# mySensor.net
KiCad netlist of a schematic drawn in Altium Designer
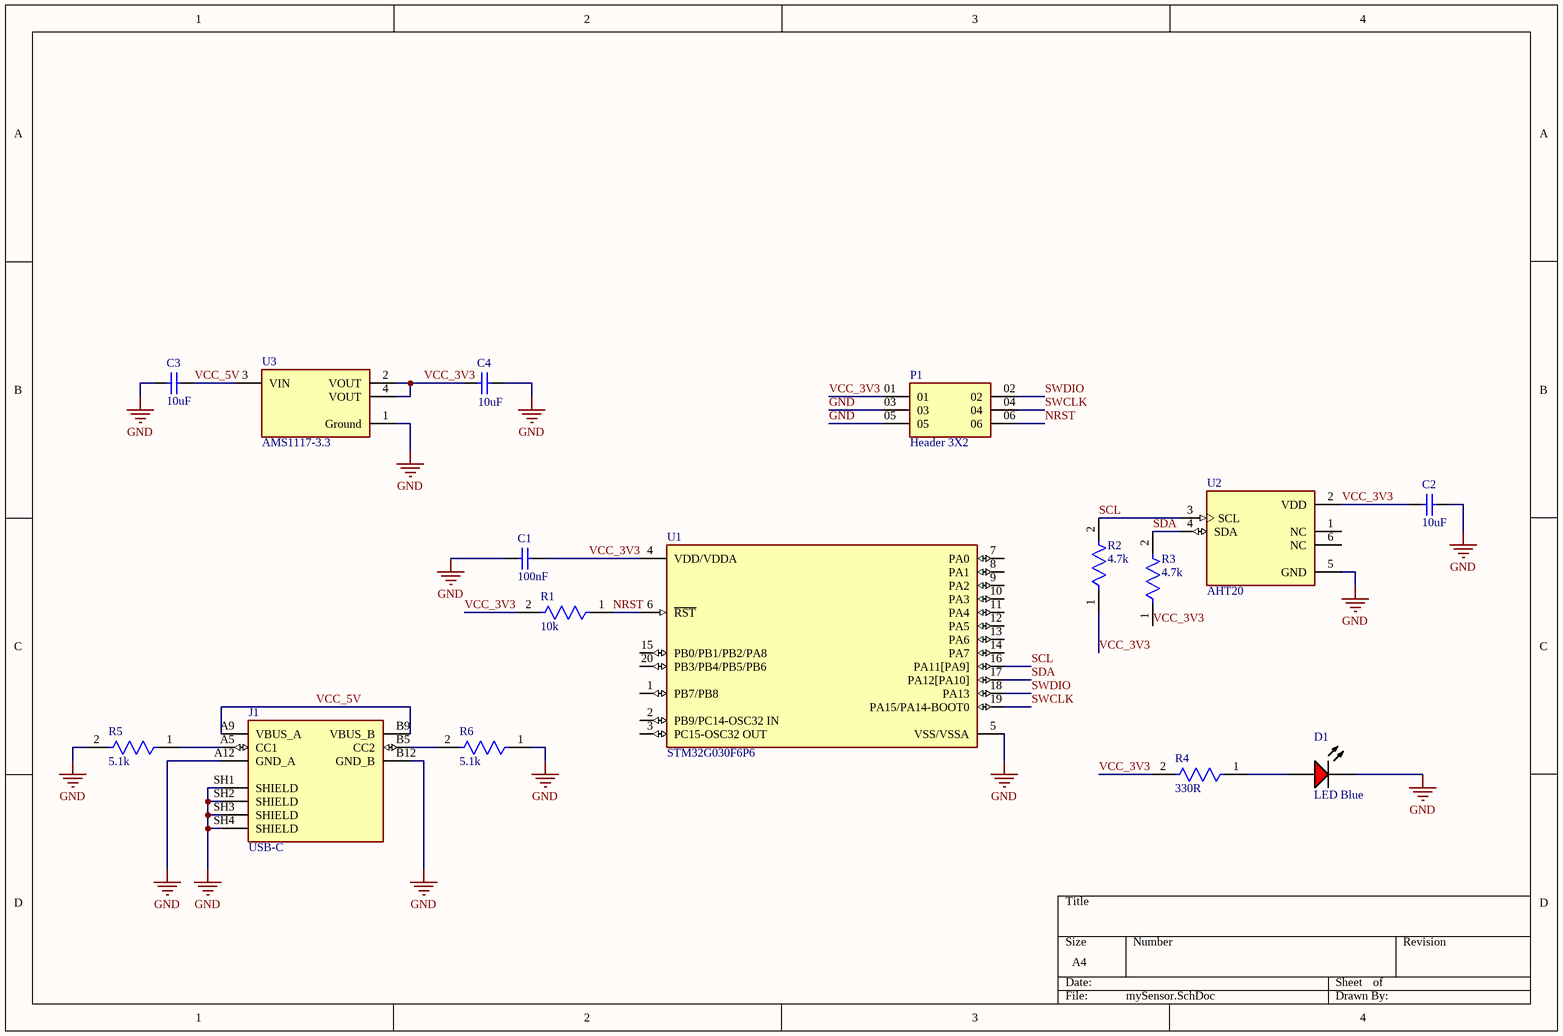
[diagram p0: mySensor.SchDoc]

(export (version "E")
  (design (tool "Eeschema 10.0.6"))
  (components
    (comp (ref "C1")
      (value "100nF")
      (footprint "CAPC1206(3216)190_L")
      (description "CAP 100nF")
      (fields (field (name "TOLERANCE") "Â±20%"))
      (libsource (lib "Altium Content Vault") (part "CAP"))
    )
    (comp (ref "C2")
      (value "10uF")
      (footprint "CAPC1206(3216)190_L")
      (description "CAP 10uF 6.3V ±20% 1206 (3216 Metric) Thickness 1.9mm SMD")
      (fields (field (name "TOLERANCE") "Â±20%"))
      (libsource (lib "Altium Content Vault") (part "CAP"))
    )
    (comp (ref "C3")
      (value "10uF")
      (footprint "CAPC1206(3216)190_L")
      (description "CAP 10uF 6.3V ±20% 1206 (3216 Metric) Thickness 1.9mm SMD")
      (fields (field (name "TOLERANCE") "Â±20%"))
      (libsource (lib "Altium Content Vault") (part "CAP"))
    )
    (comp (ref "C4")
      (value "10uF")
      (footprint "CAPC1206(3216)190_L")
      (description "CAP 10uF 6.3V ±20% 1206 (3216 Metric) Thickness 1.9mm SMD")
      (fields (field (name "TOLERANCE") "Â±20%"))
      (libsource (lib "Altium Content Vault") (part "CAP"))
    )
    (comp (ref "D1")
      (value "LED Blue")
      (footprint "LUMX-SML-LX1206IC_V")
      (description "LED Red, 65 mW, -40 to 85 degC, 2-Pin SMD, RoHS, Tape and Reel")
      (fields (field (name "MANUFACTURER") "Lumex") (field (name "PART NO") "SML-LX1206IC-TR"))
      (libsource (lib "Altium Content Vault") (part "LED-RED-AK-2"))
    )
    (comp (ref "J1")
      (value "USB-C")
      (footprint "AMPHENOL_10164359-00011LF")
      (description "USB Type C Receptacle SMT Single Row 6Pin")
      (fields (field (name "MF") "Amphenol") (field (name "MP") "1016435900011LF"))
      (libsource (lib "10164359-00011LF") (part "10164359-00011LF"))
    )
    (comp (ref "P1")
      (value "Header 3X2")
      (footprint "SAMTEC_TSM-103-02-T-DV-LC")
      (description "Conn Unshrouded Header HDR 6 POS 2.54mm Solder ST SMD Tube")
      (fields (field (name "MF") "Samtec") (field (name "MP") "TSM-103-02-T-DV-LC"))
      (libsource (lib "TSM-103-02-T-DV-LC") (part "TSM-103-02-T-DV-LC"))
    )
    (comp (ref "R1")
      (value "10k")
      (footprint "FP-CRGCQ1206-IPC_A")
      (description "CRGCQ 1206 10k 5%")
      (fields
        (field (name "MANUFACTURER") "TE Connectivity")
        (field (name "OCTOPART") "https://octopart.com/crgcq1206j4k7-te+connectivity-91018336")
      )
      (libsource (lib "Altium Content Vault") (part "1029c3af85768c4190bb7ad29bc67b5"))
    )
    (comp (ref "R2")
      (value "4.7k")
      (footprint "FP-CRGCQ1206-IPC_A")
      (description "CRGCQ 1206 4K7 5%")
      (fields
        (field (name "MANUFACTURER") "TE Connectivity")
        (field (name "OCTOPART") "https://octopart.com/crgcq1206j4k7-te+connectivity-91018336")
      )
      (libsource (lib "Altium Content Vault") (part "1029c3af85768c4190bb7ad29bc67b5"))
    )
    (comp (ref "R3")
      (value "4.7k")
      (footprint "FP-CRGCQ1206-IPC_A")
      (description "CRGCQ 1206 4K7 5%")
      (fields
        (field (name "MANUFACTURER") "TE Connectivity")
        (field (name "OCTOPART") "https://octopart.com/crgcq1206j4k7-te+connectivity-91018336")
      )
      (libsource (lib "Altium Content Vault") (part "1029c3af85768c4190bb7ad29bc67b5"))
    )
    (comp (ref "R4")
      (value "330R")
      (footprint "FP-CRGCQ1206-IPC_A")
      (description "CRGCQ 1206 330R 5%")
      (fields
        (field (name "MANUFACTURER") "TE Connectivity")
        (field (name "OCTOPART") "https://octopart.com/crgcq1206j4k7-te+connectivity-91018336")
      )
      (libsource (lib "Altium Content Vault") (part "1029c3af85768c4190bb7ad29bc67b5"))
    )
    (comp (ref "R5")
      (value "5.1k")
      (footprint "FP-CRGCQ1206-IPC_A")
      (description "CRGCQ 1206 5K1 5%")
      (fields
        (field (name "MANUFACTURER") "TE Connectivity")
        (field (name "OCTOPART") "https://octopart.com/crgcq1206j4k7-te+connectivity-91018336")
      )
      (libsource (lib "Altium Content Vault") (part "1029c3af85768c4190bb7ad29bc67b5"))
    )
    (comp (ref "R6")
      (value "5.1k")
      (footprint "FP-CRGCQ1206-IPC_A")
      (description "CRGCQ 1206 5K1 5%")
      (fields
        (field (name "MANUFACTURER") "TE Connectivity")
        (field (name "OCTOPART") "https://octopart.com/crgcq1206j4k7-te+connectivity-91018336")
      )
      (libsource (lib "Altium Content Vault") (part "1029c3af85768c4190bb7ad29bc67b5"))
    )
    (comp (ref "U1")
      (value "STM32G030F6P6")
      (footprint "FP-TSSOP20-YA-MFG")
      (description "ARM MICROCONTROLLERS - MCU")
      (fields
        (field (name "MANUFACTURER") "STMicroelectronics")
        (field (name "OCTOPART") "https://octopart.com/stm32g030f6p6-stmicroelectronics-103773023")
      )
      (libsource (lib "Altium Content Vault") (part "de2f7cf56ecdc1f1ec6ab3e49dbf5e6"))
    )
    (comp (ref "U2")
      (value "AHT20")
      (footprint "PSON100P300X300X110-6N")
      (description "Temperature and Humidity sensor")
      (fields (field (name "MF") "Asair"))
      (libsource (lib "AHT20") (part "AHT20"))
    )
    (comp (ref "U3")
      (value "AMS1117-3.3")
      (footprint "FP-AMS1117-IPC_C")
      (description "LDO Voltage Regulators 1A, 3.3V")
      (fields
        (field (name "OCTOPART") "https://octopart.com/ams1117-3.3-advanced+monolithic+systems-25899300")
        (field (name "MANUFACTURER") "Advanced Monolithic Systems")
      )
      (libsource (lib "Altium Content Vault") (part "8bdbb5f8e77002000e30dd2845d0354"))
    )
  )
  (nets
    (net (code "1") (name "/NRST") (class "Default")
      (node (ref "P1") (pin "06") (pinfunction "06_06") (pintype "passive"))
      (node (ref "R1") (pin "1") (pinfunction "1_1") (pintype "passive"))
      (node (ref "U1") (pin "6") (pinfunction "~{RST}_6") (pintype "input"))
    )
    (net (code "2") (name "/SCL") (class "Default")
      (node (ref "R2") (pin "2") (pinfunction "2_2") (pintype "passive"))
      (node (ref "U1") (pin "16") (pinfunction "PA11[PA9]_16") (pintype "bidirectional"))
      (node (ref "U2") (pin "3") (pinfunction "SCL_3") (pintype "input"))
    )
    (net (code "3") (name "/SDA") (class "Default")
      (node (ref "R3") (pin "2") (pinfunction "2_2") (pintype "passive"))
      (node (ref "U1") (pin "17") (pinfunction "PA12[PA10]_17") (pintype "bidirectional"))
      (node (ref "U2") (pin "4") (pinfunction "SDA_4") (pintype "bidirectional"))
    )
    (net (code "4") (name "/SWCLK") (class "Default")
      (node (ref "P1") (pin "04") (pinfunction "04_04") (pintype "passive"))
      (node (ref "U1") (pin "19") (pinfunction "PA15/PA14-BOOT0_19") (pintype "bidirectional"))
    )
    (net (code "5") (name "/SWDIO") (class "Default")
      (node (ref "P1") (pin "02") (pinfunction "02_02") (pintype "passive"))
      (node (ref "U1") (pin "18") (pinfunction "PA13_18") (pintype "bidirectional"))
    )
    (net (code "6") (name "/VCC_3V3") (class "Default")
      (node (ref "C1") (pin "2") (pinfunction "2_2") (pintype "passive"))
      (node (ref "C2") (pin "1") (pinfunction "1_1") (pintype "passive"))
      (node (ref "C4") (pin "1") (pinfunction "1_1") (pintype "passive"))
      (node (ref "P1") (pin "01") (pinfunction "01_01") (pintype "passive"))
      (node (ref "R1") (pin "2") (pinfunction "2_2") (pintype "passive"))
      (node (ref "R2") (pin "1") (pinfunction "1_1") (pintype "passive"))
      (node (ref "R3") (pin "1") (pinfunction "1_1") (pintype "passive"))
      (node (ref "R4") (pin "2") (pinfunction "2_2") (pintype "passive"))
      (node (ref "U1") (pin "4") (pinfunction "VDD/VDDA_4") (pintype "power_in"))
      (node (ref "U2") (pin "2") (pinfunction "VDD_2") (pintype "power_in"))
      (node (ref "U3") (pin "2") (pinfunction "VOUT_2") (pintype "passive"))
      (node (ref "U3") (pin "4") (pinfunction "VOUT_4") (pintype "passive"))
    )
    (net (code "7") (name "/VCC_5V") (class "Default")
      (node (ref "C3") (pin "2") (pinfunction "2_2") (pintype "passive"))
      (node (ref "J1") (pin "A9") (pinfunction "VBUS_A_A9") (pintype "power_in"))
      (node (ref "J1") (pin "B9") (pinfunction "VBUS_B_B9") (pintype "power_in"))
      (node (ref "U3") (pin "3") (pinfunction "VIN_3") (pintype "power_in"))
    )
    (net (code "8") (name "GND") (class "Default")
      (node (ref "C1") (pin "1") (pinfunction "1_1") (pintype "passive"))
      (node (ref "C2") (pin "2") (pinfunction "2_2") (pintype "passive"))
      (node (ref "C3") (pin "1") (pinfunction "1_1") (pintype "passive"))
      (node (ref "C4") (pin "2") (pinfunction "2_2") (pintype "passive"))
      (node (ref "D1") (pin "2") (pinfunction "K_2") (pintype "passive"))
      (node (ref "J1") (pin "A12") (pinfunction "GND_A_A12") (pintype "power_in"))
      (node (ref "J1") (pin "B12") (pinfunction "GND_B_B12") (pintype "power_in"))
      (node (ref "J1") (pin "SH1") (pinfunction "SHIELD_SH1") (pintype "passive"))
      (node (ref "J1") (pin "SH2") (pinfunction "SHIELD_SH2") (pintype "passive"))
      (node (ref "J1") (pin "SH3") (pinfunction "SHIELD_SH3") (pintype "passive"))
      (node (ref "J1") (pin "SH4") (pinfunction "SHIELD_SH4") (pintype "passive"))
      (node (ref "P1") (pin "03") (pinfunction "03_03") (pintype "passive"))
      (node (ref "P1") (pin "05") (pinfunction "05_05") (pintype "passive"))
      (node (ref "R5") (pin "2") (pinfunction "2_2") (pintype "passive"))
      (node (ref "R6") (pin "1") (pinfunction "1_1") (pintype "passive"))
      (node (ref "U1") (pin "5") (pinfunction "VSS/VSSA_5") (pintype "power_in"))
      (node (ref "U2") (pin "5") (pinfunction "GND_5") (pintype "power_in"))
      (node (ref "U3") (pin "1") (pinfunction "Ground_1") (pintype "power_in"))
    )
    (net (code "9") (name "Net-(D1-A)") (class "Default")
      (node (ref "D1") (pin "1") (pinfunction "A_1") (pintype "passive"))
      (node (ref "R4") (pin "1") (pinfunction "1_1") (pintype "passive"))
    )
    (net (code "10") (name "Net-(J1-CC1)") (class "Default")
      (node (ref "J1") (pin "A5") (pinfunction "CC1_A5") (pintype "bidirectional"))
      (node (ref "R5") (pin "1") (pinfunction "1_1") (pintype "passive"))
    )
    (net (code "11") (name "Net-(J1-CC2)") (class "Default")
      (node (ref "J1") (pin "B5") (pinfunction "CC2_B5") (pintype "bidirectional"))
      (node (ref "R6") (pin "2") (pinfunction "2_2") (pintype "passive"))
    )
    (net (code "12") (name "unconnected-(U1-PA0-Pad7)") (class "Default")
      (node (ref "U1") (pin "7") (pinfunction "PA0_7") (pintype "bidirectional"))
    )
    (net (code "13") (name "unconnected-(U1-PA1-Pad8)") (class "Default")
      (node (ref "U1") (pin "8") (pinfunction "PA1_8") (pintype "bidirectional"))
    )
    (net (code "14") (name "unconnected-(U1-PA2-Pad9)") (class "Default")
      (node (ref "U1") (pin "9") (pinfunction "PA2_9") (pintype "bidirectional"))
    )
    (net (code "15") (name "unconnected-(U1-PA3-Pad10)") (class "Default")
      (node (ref "U1") (pin "10") (pinfunction "PA3_10") (pintype "bidirectional"))
    )
    (net (code "16") (name "unconnected-(U1-PA4-Pad11)") (class "Default")
      (node (ref "U1") (pin "11") (pinfunction "PA4_11") (pintype "bidirectional"))
    )
    (net (code "17") (name "unconnected-(U1-PA5-Pad12)") (class "Default")
      (node (ref "U1") (pin "12") (pinfunction "PA5_12") (pintype "bidirectional"))
    )
    (net (code "18") (name "unconnected-(U1-PA6-Pad13)") (class "Default")
      (node (ref "U1") (pin "13") (pinfunction "PA6_13") (pintype "bidirectional"))
    )
    (net (code "19") (name "unconnected-(U1-PA7-Pad14)") (class "Default")
      (node (ref "U1") (pin "14") (pinfunction "PA7_14") (pintype "bidirectional"))
    )
    (net (code "20") (name "unconnected-(U1-PB0{slash}PB1{slash}PB2{slash}PA8-Pad15)") (class "Default")
      (node (ref "U1") (pin "15") (pinfunction "PB0/PB1/PB2/PA8_15") (pintype "bidirectional"))
    )
    (net (code "21") (name "unconnected-(U1-PB3{slash}PB4{slash}PB5{slash}PB6-Pad20)") (class "Default")
      (node (ref "U1") (pin "20") (pinfunction "PB3/PB4/PB5/PB6_20") (pintype "bidirectional"))
    )
    (net (code "22") (name "unconnected-(U1-PB7{slash}PB8-Pad1)") (class "Default")
      (node (ref "U1") (pin "1") (pinfunction "PB7/PB8_1") (pintype "bidirectional"))
    )
    (net (code "23") (name "unconnected-(U1-PB9{slash}PC14-OSC32_IN-Pad2)") (class "Default")
      (node (ref "U1") (pin "2") (pinfunction "PB9/PC14-OSC32_IN_2") (pintype "bidirectional"))
    )
    (net (code "24") (name "unconnected-(U1-PC15-OSC32_OUT-Pad3)") (class "Default")
      (node (ref "U1") (pin "3") (pinfunction "PC15-OSC32_OUT_3") (pintype "bidirectional"))
    )
    (net (code "25") (name "unconnected-(U2-NC-Pad1)") (class "Default")
      (node (ref "U2") (pin "1") (pinfunction "NC_1") (pintype "passive"))
    )
    (net (code "26") (name "unconnected-(U2-NC-Pad6)") (class "Default")
      (node (ref "U2") (pin "6") (pinfunction "NC_6") (pintype "passive"))
    )
  )
)
